# 2-MCU.net
KiCad netlist of a schematic drawn in Altium Designer
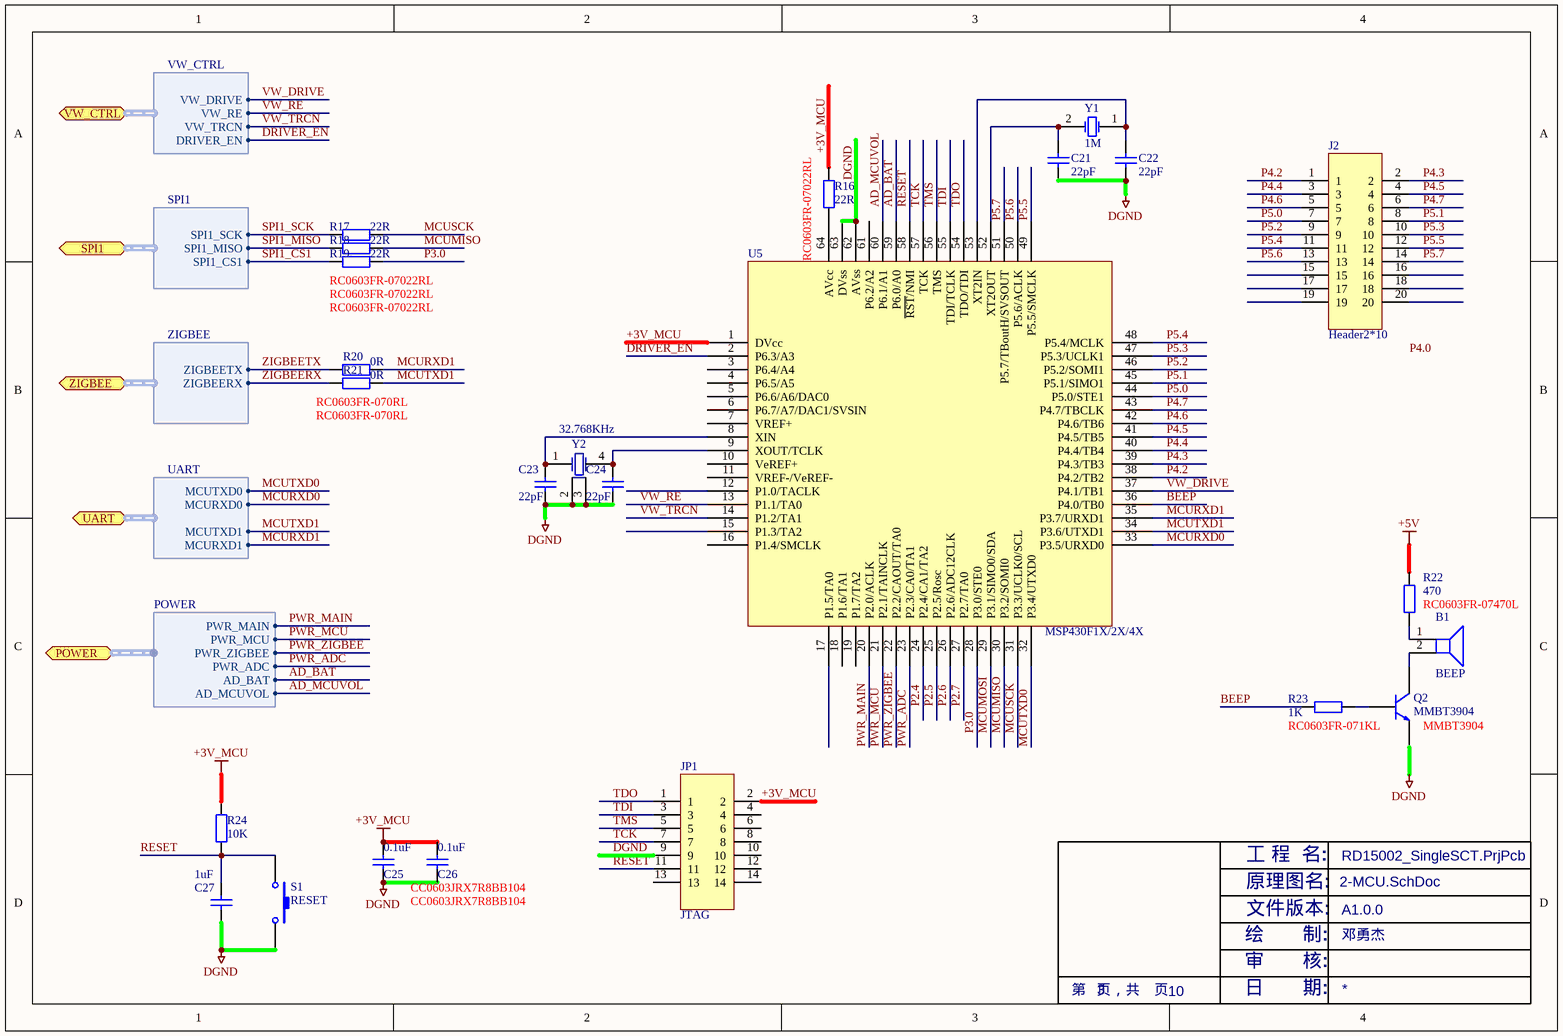
[diagram p0: 2-MCU.SchDoc]

(export (version "E")
  (design (tool "Eeschema 10.0.6"))
  (components
    (comp (ref "B1") (value "BEEP") (footprint "BUZZER-5V") (libsource (lib "woylib2015") (part "BEEP")))
    (comp (ref "C21")
      (value "22pF")
      (footprint "CC0603")
      (description "Capacitor")
      (fields (field (name "PUBLISHER") "Altium Limited"))
      (libsource (lib "Miscellaneous Devices") (part "Cap"))
    )
    (comp (ref "C22")
      (value "22pF")
      (footprint "CC0603")
      (description "Capacitor")
      (fields (field (name "PUBLISHER") "Altium Limited"))
      (libsource (lib "Miscellaneous Devices") (part "Cap"))
    )
    (comp (ref "C23")
      (value "22pF")
      (footprint "CC0603")
      (description "Capacitor")
      (fields (field (name "PUBLISHER") "Altium Limited"))
      (libsource (lib "Miscellaneous Devices") (part "Cap"))
    )
    (comp (ref "C24")
      (value "22pF")
      (footprint "CC0603")
      (description "Capacitor")
      (fields (field (name "PUBLISHER") "Altium Limited"))
      (libsource (lib "Miscellaneous Devices") (part "Cap"))
    )
    (comp (ref "C25")
      (value "0.1uF")
      (footprint "CC0603")
      (description "Capacitor")
      (fields (field (name "TYPE NO.") "CC0603JRX7R8BB104"))
      (libsource (lib "Miscellaneous Devices") (part "Cap"))
    )
    (comp (ref "C26")
      (value "0.1uF")
      (footprint "CC0603")
      (description "Capacitor")
      (fields (field (name "TYPE NO.") "CC0603JRX7R8BB104"))
      (libsource (lib "Miscellaneous Devices") (part "Cap"))
    )
    (comp (ref "C27")
      (value "1uF")
      (footprint "CC0603")
      (description "Capacitor")
      (fields (field (name "PUBLISHER") "Altium Limited"))
      (libsource (lib "Miscellaneous Devices") (part "Cap"))
    )
    (comp (ref "J2")
      (value "Header2*10")
      (footprint "IDC20-2.0MM")
      (libsource (lib "Connector") (part "Header2*10"))
    )
    (comp (ref "JP1")
      (value "JTAG")
      (footprint "IDC14-2.0MM")
      (libsource (lib "Connector") (part "Header2*7"))
    )
    (comp (ref "Q2")
      (value "MMBT3904")
      (footprint "SOT-23W")
      (fields (field (name "TYPE NO.") "MMBT3904"))
      (libsource (lib "woylib2015") (part "NPN"))
    )
    (comp (ref "R16")
      (value "22R")
      (footprint "CC0603")
      (description "Resistor")
      (fields (field (name "TYPE NO.") "RC0603FR-07022RL"))
      (libsource (lib "") (part "Res2_1"))
    )
    (comp (ref "R17")
      (value "22R")
      (footprint "CC0603")
      (description "Resistor")
      (fields (field (name "TYPE NO.") "RC0603FR-07022RL"))
      (libsource (lib "Miscellaneous Devices") (part "Res2"))
    )
    (comp (ref "R18")
      (value "22R")
      (footprint "CC0603")
      (description "Resistor")
      (fields (field (name "TYPE NO.") "RC0603FR-07022RL"))
      (libsource (lib "Miscellaneous Devices") (part "Res2"))
    )
    (comp (ref "R19")
      (value "22R")
      (footprint "CC0603")
      (description "Resistor")
      (fields (field (name "TYPE NO.") "RC0603FR-07022RL"))
      (libsource (lib "Miscellaneous Devices") (part "Res2"))
    )
    (comp (ref "R20")
      (value "0R")
      (footprint "CC0603")
      (description "Resistor")
      (fields (field (name "TYPE NO.") "RC0603FR-070RL"))
      (libsource (lib "Miscellaneous Devices") (part "Res2"))
    )
    (comp (ref "R21")
      (value "0R")
      (footprint "CC0603")
      (description "Resistor")
      (fields (field (name "TYPE NO.") "RC0603FR-070RL"))
      (libsource (lib "Miscellaneous Devices") (part "Res2"))
    )
    (comp (ref "R22")
      (value "470")
      (footprint "CC0603")
      (description "Resistor")
      (fields (field (name "TYPE NO.") "RC0603FR-07470L"))
      (libsource (lib "") (part "Res2_1"))
    )
    (comp (ref "R23")
      (value "1K")
      (footprint "CC0603")
      (description "Resistor")
      (fields (field (name "TYPE NO.") "RC0603FR-071KL"))
      (libsource (lib "Miscellaneous Devices") (part "Res2"))
    )
    (comp (ref "R24")
      (value "10K")
      (footprint "CC0603")
      (description "Resistor")
      (fields (field (name "PUBLISHER") "Altium Limited"))
      (libsource (lib "") (part "Res2_1"))
    )
    (comp (ref "S1")
      (value "RESET")
      (footprint "SPST")
      (description "Switch")
      (fields (field (name "PUBLISHER") "Altium Limited"))
      (libsource (lib "Miscellaneous Devices") (part "SW-PB"))
    )
    (comp (ref "U5")
      (value "MSP430F1X/2X/4X")
      (footprint "LQFP64")
      (libsource (lib "IC") (part "MSP430F1X/2X/4X"))
    )
    (comp (ref "Y1")
      (value "1M")
      (footprint "XCYAI")
      (description "Crystal Oscillator")
      (fields (field (name "PUBLISHER") "Altium Limited"))
      (libsource (lib "Miscellaneous Devices") (part "XTAL"))
    )
    (comp (ref "Y2") (value "32.768KHz") (footprint "MC-146") (libsource (lib "Discrete") (part "MC-146")))
  )
  (nets
    (net (code "6") (name "+3V_MCU") (class "Default")
      (node (ref "C25") (pin "2") (pinfunction "2_2") (pintype "passive"))
      (node (ref "C26") (pin "2") (pinfunction "2_2") (pintype "passive"))
      (node (ref "JP1") (pin "2") (pinfunction "2_2") (pintype "passive"))
      (node (ref "R16") (pin "2") (pinfunction "2_2") (pintype "passive"))
      (node (ref "R24") (pin "2") (pinfunction "2_2") (pintype "passive"))
      (node (ref "U5") (pin "1") (pinfunction "DVcc_1") (pintype "passive"))
    )
    (net (code "7") (name "+5V") (class "Default")
      (node (ref "R22") (pin "2") (pinfunction "2_2") (pintype "passive"))
    )
    (net (code "8") (name "/AD_BAT") (class "Default")
      (node (ref "U5") (pin "59") (pinfunction "P6.0/A0_59") (pintype "passive"))
    )
    (net (code "9") (name "/AD_MCUVOL") (class "Default")
      (node (ref "U5") (pin "60") (pinfunction "P6.1/A1_60") (pintype "passive"))
    )
    (net (code "10") (name "/BEEP") (class "Default")
      (node (ref "R23") (pin "2") (pinfunction "2_2") (pintype "passive"))
      (node (ref "U5") (pin "36") (pinfunction "P4.0/TB0_36") (pintype "passive"))
    )
    (net (code "11") (name "/DRIVER_EN") (class "Default")
      (node (ref "U5") (pin "2") (pinfunction "P6.3/A3_2") (pintype "passive"))
    )
    (net (code "12") (name "/MCUMISO") (class "Default")
      (node (ref "R18") (pin "1") (pinfunction "1_1") (pintype "passive"))
      (node (ref "U5") (pin "30") (pinfunction "P3.2/SOMI0_30") (pintype "passive"))
    )
    (net (code "13") (name "/MCUMOSI") (class "Default")
      (node (ref "U5") (pin "29") (pinfunction "P3.1/SIMO0/SDA_29") (pintype "passive"))
    )
    (net (code "14") (name "/MCURXD0") (class "Default")
      (node (ref "U5") (pin "33") (pinfunction "P3.5/URXD0_33") (pintype "passive"))
    )
    (net (code "15") (name "/MCURXD1") (class "Default")
      (node (ref "R20") (pin "1") (pinfunction "1_1") (pintype "passive"))
      (node (ref "U5") (pin "35") (pinfunction "P3.7/URXD1_35") (pintype "passive"))
    )
    (net (code "16") (name "/MCUSCK") (class "Default")
      (node (ref "R17") (pin "1") (pinfunction "1_1") (pintype "passive"))
      (node (ref "U5") (pin "31") (pinfunction "P3.3/UCLK0/SCL_31") (pintype "passive"))
    )
    (net (code "17") (name "/MCUTXD0") (class "Default")
      (node (ref "U5") (pin "32") (pinfunction "P3.4/UTXD0_32") (pintype "passive"))
    )
    (net (code "18") (name "/MCUTXD1") (class "Default")
      (node (ref "R21") (pin "1") (pinfunction "1_1") (pintype "passive"))
      (node (ref "U5") (pin "34") (pinfunction "P3.6/UTXD1_34") (pintype "passive"))
    )
    (net (code "19") (name "/P2.4") (class "Default")
      (node (ref "U5") (pin "24") (pinfunction "P2.4/CA1/TA2_24") (pintype "passive"))
    )
    (net (code "20") (name "/P2.5") (class "Default")
      (node (ref "U5") (pin "25") (pinfunction "P2.5/Rosc_25") (pintype "passive"))
    )
    (net (code "21") (name "/P2.6") (class "Default")
      (node (ref "U5") (pin "26") (pinfunction "P2.6/ADC12CLK_26") (pintype "passive"))
    )
    (net (code "22") (name "/P2.7") (class "Default")
      (node (ref "U5") (pin "27") (pinfunction "P2.7/TA0_27") (pintype "passive"))
    )
    (net (code "23") (name "/P3.0") (class "Default")
      (node (ref "R19") (pin "1") (pinfunction "1_1") (pintype "passive"))
      (node (ref "U5") (pin "28") (pinfunction "P3.0/STE0_28") (pintype "passive"))
    )
    (net (code "25") (name "/P4.2") (class "Default")
      (node (ref "J2") (pin "1") (pinfunction "1_1") (pintype "passive"))
      (node (ref "U5") (pin "38") (pinfunction "P4.2/TB2_38") (pintype "passive"))
    )
    (net (code "26") (name "/P4.3") (class "Default")
      (node (ref "J2") (pin "2") (pinfunction "2_2") (pintype "passive"))
      (node (ref "U5") (pin "39") (pinfunction "P4.3/TB3_39") (pintype "passive"))
    )
    (net (code "27") (name "/P4.4") (class "Default")
      (node (ref "J2") (pin "3") (pinfunction "3_3") (pintype "passive"))
      (node (ref "U5") (pin "40") (pinfunction "P4.4/TB4_40") (pintype "passive"))
    )
    (net (code "28") (name "/P4.5") (class "Default")
      (node (ref "J2") (pin "4") (pinfunction "4_4") (pintype "passive"))
      (node (ref "U5") (pin "41") (pinfunction "P4.5/TB5_41") (pintype "passive"))
    )
    (net (code "29") (name "/P4.6") (class "Default")
      (node (ref "J2") (pin "5") (pinfunction "5_5") (pintype "passive"))
      (node (ref "U5") (pin "42") (pinfunction "P4.6/TB6_42") (pintype "passive"))
    )
    (net (code "30") (name "/P4.7") (class "Default")
      (node (ref "J2") (pin "6") (pinfunction "6_6") (pintype "passive"))
      (node (ref "U5") (pin "43") (pinfunction "P4.7/TBCLK_43") (pintype "passive"))
    )
    (net (code "31") (name "/P5.0") (class "Default")
      (node (ref "J2") (pin "7") (pinfunction "7_7") (pintype "passive"))
      (node (ref "U5") (pin "44") (pinfunction "P5.0/STE1_44") (pintype "passive"))
    )
    (net (code "32") (name "/P5.1") (class "Default")
      (node (ref "J2") (pin "8") (pinfunction "8_8") (pintype "passive"))
      (node (ref "U5") (pin "45") (pinfunction "P5.1/SIMO1_45") (pintype "passive"))
    )
    (net (code "33") (name "/P5.2") (class "Default")
      (node (ref "J2") (pin "9") (pinfunction "9_9") (pintype "passive"))
      (node (ref "U5") (pin "46") (pinfunction "P5.2/SOMI1_46") (pintype "passive"))
    )
    (net (code "34") (name "/P5.3") (class "Default")
      (node (ref "J2") (pin "10") (pinfunction "10_10") (pintype "passive"))
      (node (ref "U5") (pin "47") (pinfunction "P5.3/UCLK1_47") (pintype "passive"))
    )
    (net (code "35") (name "/P5.4") (class "Default")
      (node (ref "J2") (pin "11") (pinfunction "11_11") (pintype "passive"))
      (node (ref "U5") (pin "48") (pinfunction "P5.4/MCLK_48") (pintype "passive"))
    )
    (net (code "36") (name "/P5.5") (class "Default")
      (node (ref "J2") (pin "12") (pinfunction "12_12") (pintype "passive"))
      (node (ref "U5") (pin "49") (pinfunction "P5.5/SMCLK_49") (pintype "passive"))
    )
    (net (code "37") (name "/P5.6") (class "Default")
      (node (ref "J2") (pin "13") (pinfunction "13_13") (pintype "passive"))
      (node (ref "U5") (pin "50") (pinfunction "P5.6/ACLK_50") (pintype "passive"))
    )
    (net (code "38") (name "/P5.7") (class "Default")
      (node (ref "J2") (pin "14") (pinfunction "14_14") (pintype "passive"))
      (node (ref "U5") (pin "51") (pinfunction "P5.7/TBoutH/SVSOUT_51") (pintype "passive"))
    )
    (net (code "39") (name "/PWR_ADC") (class "Default")
      (node (ref "U5") (pin "23") (pinfunction "P2.3/CA0/TA1_23") (pintype "passive"))
    )
    (net (code "40") (name "/PWR_MAIN") (class "Default")
      (node (ref "U5") (pin "20") (pinfunction "P2.0/ACLK_20") (pintype "passive"))
    )
    (net (code "41") (name "/PWR_MCU") (class "Default")
      (node (ref "U5") (pin "21") (pinfunction "P2.1/TAINCLK_21") (pintype "passive"))
    )
    (net (code "42") (name "/PWR_ZIGBEE") (class "Default")
      (node (ref "U5") (pin "22") (pinfunction "P2.2/CAOUT/TA0_22") (pintype "passive"))
    )
    (net (code "43") (name "/RESET") (class "Default")
      (node (ref "C27") (pin "2") (pinfunction "2_2") (pintype "passive"))
      (node (ref "JP1") (pin "11") (pinfunction "11_11") (pintype "passive"))
      (node (ref "R24") (pin "1") (pinfunction "1_1") (pintype "passive"))
      (node (ref "S1") (pin "2") (pinfunction "2_2") (pintype "passive"))
      (node (ref "U5") (pin "58") (pinfunction "~{RST}/NMI_58") (pintype "passive"))
    )
    (net (code "44") (name "/SPI1_CS1") (class "Default")
      (node (ref "R19") (pin "2") (pinfunction "2_2") (pintype "passive"))
    )
    (net (code "45") (name "/SPI1_MISO") (class "Default")
      (node (ref "R18") (pin "2") (pinfunction "2_2") (pintype "passive"))
    )
    (net (code "46") (name "/SPI1_SCK") (class "Default")
      (node (ref "R17") (pin "2") (pinfunction "2_2") (pintype "passive"))
    )
    (net (code "47") (name "/TCK") (class "Default")
      (node (ref "JP1") (pin "7") (pinfunction "7_7") (pintype "passive"))
      (node (ref "U5") (pin "57") (pinfunction "TCK_57") (pintype "passive"))
    )
    (net (code "48") (name "/TDI") (class "Default")
      (node (ref "JP1") (pin "3") (pinfunction "3_3") (pintype "passive"))
      (node (ref "U5") (pin "55") (pinfunction "TDI/TCLK_55") (pintype "passive"))
    )
    (net (code "49") (name "/TDO") (class "Default")
      (node (ref "JP1") (pin "1") (pinfunction "1_1") (pintype "passive"))
      (node (ref "U5") (pin "54") (pinfunction "TDO/TDI_54") (pintype "passive"))
    )
    (net (code "50") (name "/TMS") (class "Default")
      (node (ref "JP1") (pin "5") (pinfunction "5_5") (pintype "passive"))
      (node (ref "U5") (pin "56") (pinfunction "TMS_56") (pintype "passive"))
    )
    (net (code "51") (name "/VW_DRIVE") (class "Default")
      (node (ref "U5") (pin "37") (pinfunction "P4.1/TB1_37") (pintype "passive"))
    )
    (net (code "52") (name "/VW_RE") (class "Default")
      (node (ref "U5") (pin "13") (pinfunction "P1.1/TA0_13") (pintype "passive"))
    )
    (net (code "53") (name "/VW_TRCN") (class "Default")
      (node (ref "U5") (pin "14") (pinfunction "P1.2/TA1_14") (pintype "passive"))
    )
    (net (code "54") (name "/ZIGBEERX") (class "Default")
      (node (ref "R21") (pin "2") (pinfunction "2_2") (pintype "passive"))
    )
    (net (code "55") (name "/ZIGBEETX") (class "Default")
      (node (ref "R20") (pin "2") (pinfunction "2_2") (pintype "passive"))
    )
    (net (code "61") (name "DGND") (class "Default")
      (node (ref "C21") (pin "1") (pinfunction "1_1") (pintype "passive"))
      (node (ref "C22") (pin "1") (pinfunction "1_1") (pintype "passive"))
      (node (ref "C23") (pin "2") (pinfunction "2_2") (pintype "passive"))
      (node (ref "C24") (pin "2") (pinfunction "2_2") (pintype "passive"))
      (node (ref "C25") (pin "1") (pinfunction "1_1") (pintype "passive"))
      (node (ref "C26") (pin "1") (pinfunction "1_1") (pintype "passive"))
      (node (ref "C27") (pin "1") (pinfunction "1_1") (pintype "passive"))
      (node (ref "JP1") (pin "9") (pinfunction "9_9") (pintype "passive"))
      (node (ref "Q2") (pin "2") (pinfunction "2_2") (pintype "passive"))
      (node (ref "S1") (pin "1") (pinfunction "1_1") (pintype "passive"))
      (node (ref "U5") (pin "62") (pinfunction "AVss_62") (pintype "passive"))
      (node (ref "U5") (pin "63") (pinfunction "DVss_63") (pintype "passive"))
      (node (ref "Y2") (pin "2") (pinfunction "GND_2") (pintype "passive"))
      (node (ref "Y2") (pin "3") (pinfunction "GND_3") (pintype "passive"))
    )
    (net (code "62") (name "Net-(B1-Pad1)") (class "Default")
      (node (ref "B1") (pin "1") (pinfunction "1_1") (pintype "passive"))
      (node (ref "R22") (pin "1") (pinfunction "1_1") (pintype "passive"))
    )
    (net (code "63") (name "Net-(B1-Pad2)") (class "Default")
      (node (ref "B1") (pin "2") (pinfunction "2_2") (pintype "passive"))
      (node (ref "Q2") (pin "3") (pinfunction "3_3") (pintype "passive"))
    )
    (net (code "64") (name "Net-(Q2-Pad1)") (class "Default")
      (node (ref "Q2") (pin "1") (pinfunction "1_1") (pintype "passive"))
      (node (ref "R23") (pin "1") (pinfunction "1_1") (pintype "passive"))
    )
    (net (code "65") (name "Net-(U5-AVcc)") (class "Default")
      (node (ref "R16") (pin "1") (pinfunction "1_1") (pintype "passive"))
      (node (ref "U5") (pin "64") (pinfunction "AVcc_64") (pintype "passive"))
    )
    (net (code "66") (name "Net-(U5-XIN)") (class "Default")
      (node (ref "C23") (pin "1") (pinfunction "1_1") (pintype "passive"))
      (node (ref "U5") (pin "8") (pinfunction "XIN_8") (pintype "passive"))
      (node (ref "Y2") (pin "1") (pinfunction "X1_1") (pintype "passive"))
    )
    (net (code "67") (name "Net-(U5-XOUT{slash}TCLK)") (class "Default")
      (node (ref "C24") (pin "1") (pinfunction "1_1") (pintype "passive"))
      (node (ref "U5") (pin "9") (pinfunction "XOUT/TCLK_9") (pintype "passive"))
      (node (ref "Y2") (pin "4") (pinfunction "X2_4") (pintype "passive"))
    )
    (net (code "68") (name "Net-(U5-XT2IN)") (class "Default")
      (node (ref "C22") (pin "2") (pinfunction "2_2") (pintype "passive"))
      (node (ref "U5") (pin "53") (pinfunction "XT2IN_53") (pintype "passive"))
      (node (ref "Y1") (pin "1") (pinfunction "OSC1_1") (pintype "passive"))
    )
    (net (code "69") (name "Net-(U5-XT2OUT)") (class "Default")
      (node (ref "C21") (pin "2") (pinfunction "2_2") (pintype "passive"))
      (node (ref "U5") (pin "52") (pinfunction "XT2OUT_52") (pintype "passive"))
      (node (ref "Y1") (pin "2") (pinfunction "OSC2_2") (pintype "passive"))
    )
    (net (code "70") (name "unconnected-(J2-Pad15)") (class "Default")
      (node (ref "J2") (pin "15") (pinfunction "15_15") (pintype "passive"))
    )
    (net (code "71") (name "unconnected-(J2-Pad16)") (class "Default")
      (node (ref "J2") (pin "16") (pinfunction "16_16") (pintype "passive"))
    )
    (net (code "72") (name "unconnected-(J2-Pad17)") (class "Default")
      (node (ref "J2") (pin "17") (pinfunction "17_17") (pintype "passive"))
    )
    (net (code "73") (name "unconnected-(J2-Pad18)") (class "Default")
      (node (ref "J2") (pin "18") (pinfunction "18_18") (pintype "passive"))
    )
    (net (code "74") (name "unconnected-(J2-Pad19)") (class "Default")
      (node (ref "J2") (pin "19") (pinfunction "19_19") (pintype "passive"))
    )
    (net (code "75") (name "unconnected-(J2-Pad20)") (class "Default")
      (node (ref "J2") (pin "20") (pinfunction "20_20") (pintype "passive"))
    )
    (net (code "76") (name "unconnected-(JP1-Pad4)") (class "Default")
      (node (ref "JP1") (pin "4") (pinfunction "4_4") (pintype "passive"))
    )
    (net (code "77") (name "unconnected-(JP1-Pad6)") (class "Default")
      (node (ref "JP1") (pin "6") (pinfunction "6_6") (pintype "passive"))
    )
    (net (code "78") (name "unconnected-(JP1-Pad8)") (class "Default")
      (node (ref "JP1") (pin "8") (pinfunction "8_8") (pintype "passive"))
    )
    (net (code "79") (name "unconnected-(JP1-Pad10)") (class "Default")
      (node (ref "JP1") (pin "10") (pinfunction "10_10") (pintype "passive"))
    )
    (net (code "80") (name "unconnected-(JP1-Pad12)") (class "Default")
      (node (ref "JP1") (pin "12") (pinfunction "12_12") (pintype "passive"))
    )
    (net (code "81") (name "unconnected-(JP1-Pad13)") (class "Default")
      (node (ref "JP1") (pin "13") (pinfunction "13_13") (pintype "passive"))
    )
    (net (code "82") (name "unconnected-(JP1-Pad14)") (class "Default")
      (node (ref "JP1") (pin "14") (pinfunction "14_14") (pintype "passive"))
    )
    (net (code "83") (name "unconnected-(U5-P1.0{slash}TACLK-Pad12)") (class "Default")
      (node (ref "U5") (pin "12") (pinfunction "P1.0/TACLK_12") (pintype "passive"))
    )
    (net (code "84") (name "unconnected-(U5-P1.3{slash}TA2-Pad15)") (class "Default")
      (node (ref "U5") (pin "15") (pinfunction "P1.3/TA2_15") (pintype "passive"))
    )
    (net (code "85") (name "unconnected-(U5-P1.4{slash}SMCLK-Pad16)") (class "Default")
      (node (ref "U5") (pin "16") (pinfunction "P1.4/SMCLK_16") (pintype "passive"))
    )
    (net (code "86") (name "unconnected-(U5-P1.5{slash}TA0-Pad17)") (class "Default")
      (node (ref "U5") (pin "17") (pinfunction "P1.5/TA0_17") (pintype "passive"))
    )
    (net (code "87") (name "unconnected-(U5-P1.6{slash}TA1-Pad18)") (class "Default")
      (node (ref "U5") (pin "18") (pinfunction "P1.6/TA1_18") (pintype "passive"))
    )
    (net (code "88") (name "unconnected-(U5-P1.7{slash}TA2-Pad19)") (class "Default")
      (node (ref "U5") (pin "19") (pinfunction "P1.7/TA2_19") (pintype "passive"))
    )
    (net (code "89") (name "unconnected-(U5-P6.2{slash}A2-Pad61)") (class "Default")
      (node (ref "U5") (pin "61") (pinfunction "P6.2/A2_61") (pintype "passive"))
    )
    (net (code "90") (name "unconnected-(U5-P6.4{slash}A4-Pad3)") (class "Default")
      (node (ref "U5") (pin "3") (pinfunction "P6.4/A4_3") (pintype "passive"))
    )
    (net (code "91") (name "unconnected-(U5-P6.5{slash}A5-Pad4)") (class "Default")
      (node (ref "U5") (pin "4") (pinfunction "P6.5/A5_4") (pintype "passive"))
    )
    (net (code "92") (name "unconnected-(U5-P6.6{slash}A6{slash}DAC0-Pad5)") (class "Default")
      (node (ref "U5") (pin "5") (pinfunction "P6.6/A6/DAC0_5") (pintype "passive"))
    )
    (net (code "93") (name "unconnected-(U5-P6.7{slash}A7{slash}DAC1{slash}SVSIN-Pad6)") (class "Default")
      (node (ref "U5") (pin "6") (pinfunction "P6.7/A7/DAC1/SVSIN_6") (pintype "passive"))
    )
    (net (code "94") (name "unconnected-(U5-VREF+-Pad7)") (class "Default")
      (node (ref "U5") (pin "7") (pinfunction "VREF+_7") (pintype "passive"))
    )
    (net (code "95") (name "unconnected-(U5-VREF-{slash}VeREF--Pad11)") (class "Default")
      (node (ref "U5") (pin "11") (pinfunction "VREF-/VeREF-_11") (pintype "passive"))
    )
    (net (code "96") (name "unconnected-(U5-VeREF+-Pad10)") (class "Default")
      (node (ref "U5") (pin "10") (pinfunction "VeREF+_10") (pintype "passive"))
    )
  )
)
